# HIP4082.net
KiCad netlist of a schematic drawn in EasyEDA Pro
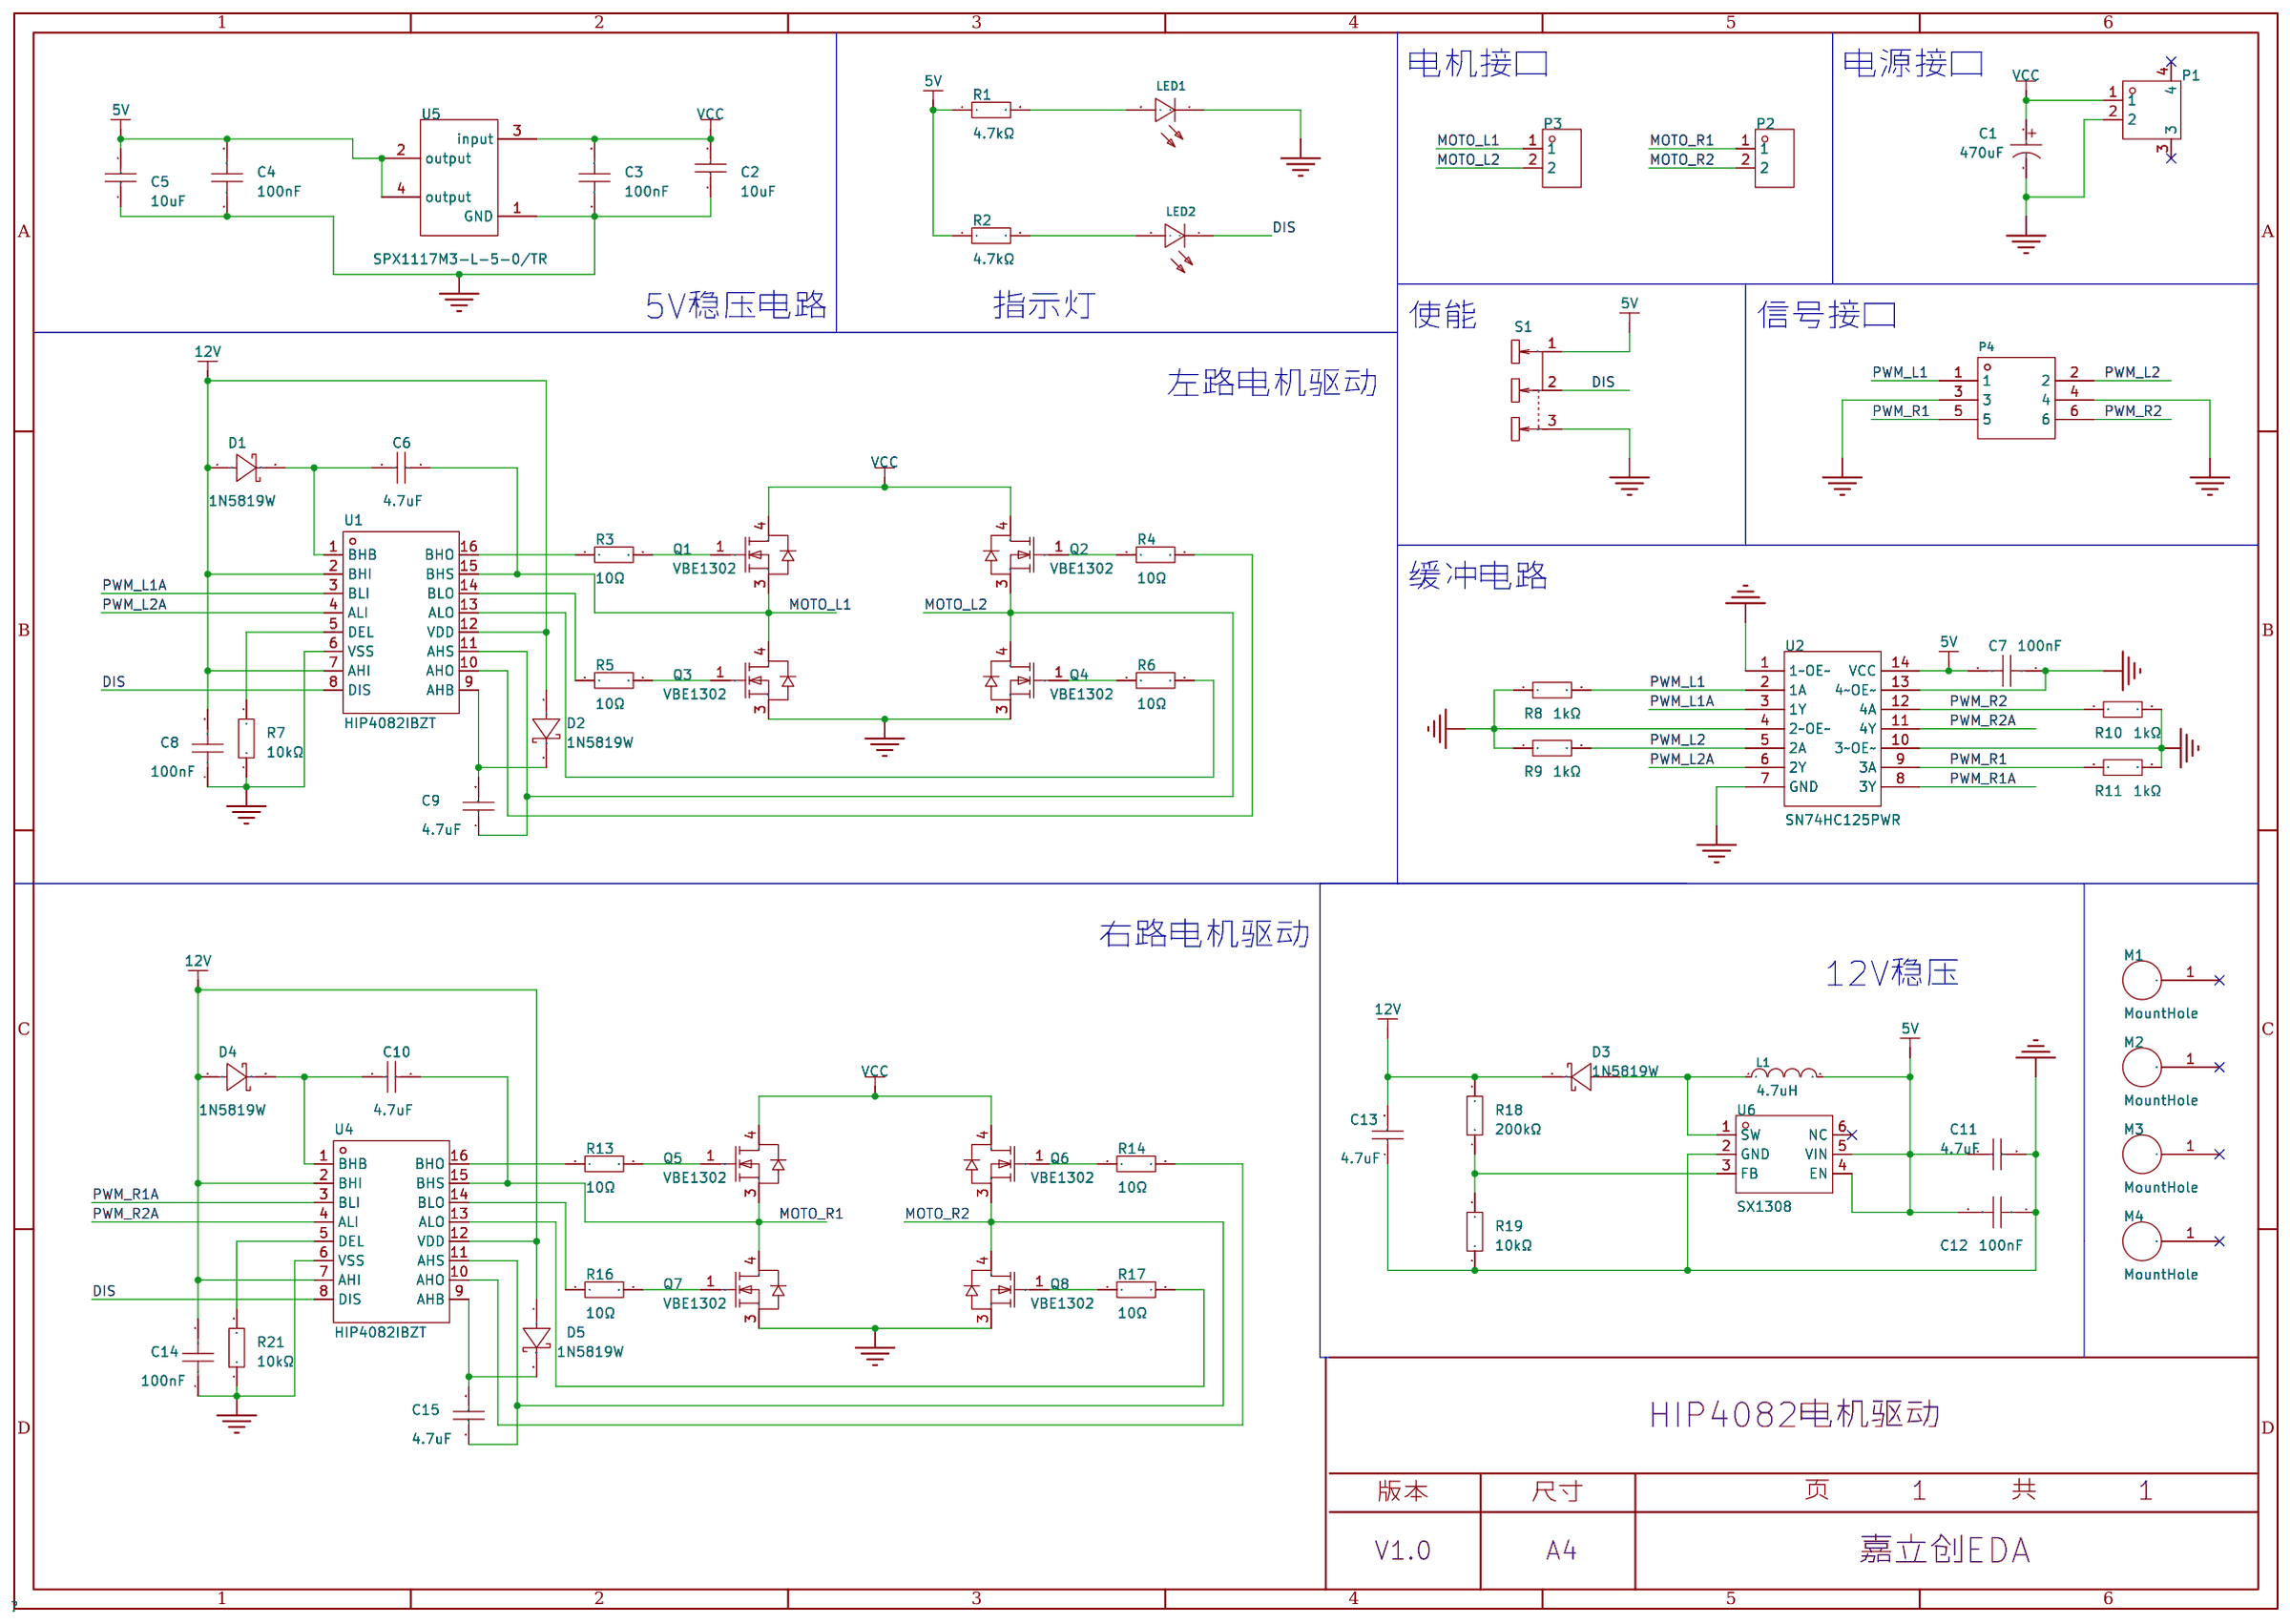
[diagram p0: schematic sheet]

(export (version "E")
  (design (tool "Eeschema 10.0.6"))
  (components
    (comp (ref "C1")
      (value "470uF")
      (footprint "easyedapro:CAP-TH_BD8.0-P3.50-D0.6-FD")
      (description "容值:470uF;精度:±20%;额定电压:25V;")
      (fields
        (field (name "Manufacturer Part") "KM477M025F12RR0VH2FP0")
        (field (name "Manufacturer") "CX(承兴)")
      )
      (libsource (lib "easyedapro") (part "470uF 25V 8*12"))
    )
    (comp (ref "C2")
      (value "10uF")
      (footprint "easyedapro:C0805")
      (description "容值:10uF;精度:±10%;额定电压:25V;材质(温度系数):X5R;")
      (fields
        (field (name "Manufacturer Part") "CL21A106KAYNNNE")
        (field (name "Manufacturer") "SAMSUNG(三星)")
      )
      (libsource (lib "easyedapro") (part "CL21A106KAYNNNE"))
    )
    (comp (ref "C3")
      (value "100nF")
      (footprint "easyedapro:C0603")
      (libsource (lib "easyedapro") (part "CapAcitance"))
    )
    (comp (ref "C4")
      (value "100nF")
      (footprint "easyedapro:C0603")
      (libsource (lib "easyedapro") (part "CapAcitance"))
    )
    (comp (ref "C5")
      (value "10uF")
      (footprint "easyedapro:C0805")
      (description "容值:10uF;精度:±10%;额定电压:25V;材质(温度系数):X5R;")
      (fields
        (field (name "Manufacturer Part") "CL21A106KAYNNNE")
        (field (name "Manufacturer") "SAMSUNG(三星)")
      )
      (libsource (lib "easyedapro") (part "CL21A106KAYNNNE"))
    )
    (comp (ref "C6")
      (value "4.7uF")
      (footprint "easyedapro:C0603")
      (description "容值:4.7uF;精度:±10%;额定电压:16V;材质(温度系数):X5R;")
      (fields
        (field (name "Manufacturer Part") "CL10A475KO8NNNC")
        (field (name "Manufacturer") "SAMSUNG(三星)")
      )
      (libsource (lib "easyedapro") (part "CL10A475KO8NNNC"))
    )
    (comp (ref "C7")
      (value "100nF")
      (footprint "easyedapro:C0603")
      (libsource (lib "easyedapro") (part "CapAcitance"))
    )
    (comp (ref "C8")
      (value "100nF")
      (footprint "easyedapro:C0603")
      (libsource (lib "easyedapro") (part "CapAcitance"))
    )
    (comp (ref "C9")
      (value "4.7uF")
      (footprint "easyedapro:C0603")
      (description "容值:4.7uF;精度:±10%;额定电压:16V;材质(温度系数):X5R;")
      (fields
        (field (name "Manufacturer Part") "CL10A475KO8NNNC")
        (field (name "Manufacturer") "SAMSUNG(三星)")
      )
      (libsource (lib "easyedapro") (part "CL10A475KO8NNNC"))
    )
    (comp (ref "C10")
      (value "4.7uF")
      (footprint "easyedapro:C0603")
      (description "容值:4.7uF;精度:±10%;额定电压:16V;材质(温度系数):X5R;")
      (fields
        (field (name "Manufacturer Part") "CL10A475KO8NNNC")
        (field (name "Manufacturer") "SAMSUNG(三星)")
      )
      (libsource (lib "easyedapro") (part "CL10A475KO8NNNC"))
    )
    (comp (ref "C11")
      (value "4.7uF")
      (footprint "easyedapro:C0603")
      (description "容值:4.7uF;精度:±10%;额定电压:16V;材质(温度系数):X5R;")
      (fields
        (field (name "Manufacturer Part") "CL10A475KO8NNNC")
        (field (name "Manufacturer") "SAMSUNG(三星)")
      )
      (libsource (lib "easyedapro") (part "CL10A475KO8NNNC"))
    )
    (comp (ref "C12")
      (value "100nF")
      (footprint "easyedapro:C0603")
      (libsource (lib "easyedapro") (part "CapAcitance"))
    )
    (comp (ref "C13")
      (value "4.7uF")
      (footprint "easyedapro:C0603")
      (description "容值:4.7uF;精度:±10%;额定电压:16V;材质(温度系数):X5R;")
      (fields
        (field (name "Manufacturer Part") "CL10A475KO8NNNC")
        (field (name "Manufacturer") "SAMSUNG(三星)")
      )
      (libsource (lib "easyedapro") (part "CL10A475KO8NNNC"))
    )
    (comp (ref "C14")
      (value "100nF")
      (footprint "easyedapro:C0603")
      (libsource (lib "easyedapro") (part "CapAcitance"))
    )
    (comp (ref "C15")
      (value "4.7uF")
      (footprint "easyedapro:C0603")
      (description "容值:4.7uF;精度:±10%;额定电压:16V;材质(温度系数):X5R;")
      (fields
        (field (name "Manufacturer Part") "CL10A475KO8NNNC")
        (field (name "Manufacturer") "SAMSUNG(三星)")
      )
      (libsource (lib "easyedapro") (part "CL10A475KO8NNNC"))
    )
    (comp (ref "D1")
      (value "1N5819W")
      (footprint "easyedapro:SOD-123_L2.7-W1.6-LS3.7-R-RD")
      (description "二极管配置:独立式;直流反向耐压(Vr):40V;平均整流电流(Io):350mA;正向压降(Vf):600mV@200mA;反向电流(Ir):5uA@30V;")
      (fields (field (name "Manufacturer") "JSMSEMI(杰盛微)"))
      (libsource (lib "easyedapro") (part "1N5819W_C963381"))
    )
    (comp (ref "D2")
      (value "1N5819W")
      (footprint "easyedapro:SOD-123_L2.7-W1.6-LS3.7-R-RD")
      (description "二极管配置:独立式;直流反向耐压(Vr):40V;平均整流电流(Io):350mA;正向压降(Vf):600mV@200mA;反向电流(Ir):5uA@30V;")
      (fields (field (name "Manufacturer") "JSMSEMI(杰盛微)"))
      (libsource (lib "easyedapro") (part "1N5819W_C963381"))
    )
    (comp (ref "D3")
      (value "1N5819W")
      (footprint "easyedapro:SOD-123_L2.7-W1.6-LS3.7-R-RD")
      (description "二极管配置:独立式;直流反向耐压(Vr):40V;平均整流电流(Io):350mA;正向压降(Vf):600mV@200mA;反向电流(Ir):5uA@30V;")
      (fields (field (name "Manufacturer") "JSMSEMI(杰盛微)"))
      (libsource (lib "easyedapro") (part "1N5819W_C963381"))
    )
    (comp (ref "D4")
      (value "1N5819W")
      (footprint "easyedapro:SOD-123_L2.7-W1.6-LS3.7-R-RD")
      (description "二极管配置:独立式;直流反向耐压(Vr):40V;平均整流电流(Io):350mA;正向压降(Vf):600mV@200mA;反向电流(Ir):5uA@30V;")
      (fields (field (name "Manufacturer") "JSMSEMI(杰盛微)"))
      (libsource (lib "easyedapro") (part "1N5819W_C963381"))
    )
    (comp (ref "D5")
      (value "1N5819W")
      (footprint "easyedapro:SOD-123_L2.7-W1.6-LS3.7-R-RD")
      (description "二极管配置:独立式;直流反向耐压(Vr):40V;平均整流电流(Io):350mA;正向压降(Vf):600mV@200mA;反向电流(Ir):5uA@30V;")
      (fields (field (name "Manufacturer") "JSMSEMI(杰盛微)"))
      (libsource (lib "easyedapro") (part "1N5819W_C963381"))
    )
    (comp (ref "L1")
      (value "4.7uH")
      (footprint "easyedapro:IND-SMD_L5.4-W5.2_FXL0530")
      (description "电感值:4.7uH;精度:±20%;额定电流:4.5A;饱和电流(Isat):5A;")
      (fields (field (name "Manufacturer Part") "FXL0530-4R7-M") (field (name "Manufacturer") "cjiang(长江微电)"))
      (libsource (lib "easyedapro") (part "FXL0530-4R7-M"))
    )
    (comp (ref "LED1")
      (value "NCD0603R1")
      (footprint "easyedapro:LED0603-RD_RED")
      (description "发光颜色:红灯;")
      (fields (field (name "Manufacturer") "国星光电"))
      (libsource (lib "easyedapro") (part "FC-DA1608HRK-620D"))
    )
    (comp (ref "LED2")
      (value "NCD0603B1")
      (footprint "easyedapro:LED0603-RD")
      (description "发光颜色:蓝灯;")
      (fields (field (name "Manufacturer") "国星光电"))
      (libsource (lib "easyedapro") (part "FC-DA1608BK-470H10"))
    )
    (comp (ref "M1")
      (value "MountHole")
      (footprint "easyedapro:M3-MountSlot")
      (libsource (lib "easyedapro") (part "MountHole"))
    )
    (comp (ref "M2")
      (value "MountHole")
      (footprint "easyedapro:M3-MountSlot")
      (libsource (lib "easyedapro") (part "MountHole"))
    )
    (comp (ref "M3")
      (value "MountHole")
      (footprint "easyedapro:M3-MountSlot")
      (libsource (lib "easyedapro") (part "MountHole"))
    )
    (comp (ref "M4")
      (value "MountHole")
      (footprint "easyedapro:M3-MountSlot")
      (libsource (lib "easyedapro") (part "MountHole"))
    )
    (comp (ref "P1")
      (value "XT30PW-M")
      (footprint "easyedapro:CONN-TH_XT30PW-M")
      (description "Socket,DCsupply,XT30,male,PIN:2")
      (fields (field (name "Manufacturer") "AMASS(艾迈斯)"))
      (libsource (lib "easyedapro") (part "XT30PW-M"))
    )
    (comp (ref "P2")
      (value "XT30U-M")
      (footprint "easyedapro:CONN-TH_XT30U-M")
      (description "模型插头轻量版锂电池插头")
      (fields (field (name "Manufacturer") "AMASS(艾迈斯)"))
      (libsource (lib "easyedapro") (part "XT30U-M"))
    )
    (comp (ref "P3")
      (value "XT30U-M")
      (footprint "easyedapro:CONN-TH_XT30U-M")
      (description "模型插头轻量版锂电池插头")
      (fields (field (name "Manufacturer") "AMASS(艾迈斯)"))
      (libsource (lib "easyedapro") (part "XT30U-M"))
    )
    (comp (ref "P4")
      (value "75869-131LF")
      (footprint "easyedapro:CONN-TH_6P-P2.54_75869-131LF")
      (description "参考系列:-;间距:2.54mm;插针结构:2x3P;排数:2;每排PIN数:3;行距:2.54mm;安装方式:-;触头材质:磷青铜;")
      (fields (field (name "Manufacturer") "Amphenol"))
      (libsource (lib "easyedapro") (part "75869-131LF"))
    )
    (comp (ref "Q1")
      (value "VBE1302")
      (footprint "easyedapro:TO-252-2_L6.6-W6.1-P4.58-LS9.9-TL-1")
      (fields (field (name "Manufacturer") "VBsemi(微碧)"))
      (libsource (lib "easyedapro") (part "VBE1302"))
    )
    (comp (ref "Q2")
      (value "VBE1302")
      (footprint "easyedapro:TO-252-2_L6.6-W6.1-P4.58-LS9.9-TL-1")
      (fields (field (name "Manufacturer") "VBsemi(微碧)"))
      (libsource (lib "easyedapro") (part "VBE1302"))
    )
    (comp (ref "Q3")
      (value "VBE1302")
      (footprint "easyedapro:TO-252-2_L6.6-W6.1-P4.58-LS9.9-TL-1")
      (fields (field (name "Manufacturer") "VBsemi(微碧)"))
      (libsource (lib "easyedapro") (part "VBE1302"))
    )
    (comp (ref "Q4")
      (value "VBE1302")
      (footprint "easyedapro:TO-252-2_L6.6-W6.1-P4.58-LS9.9-TL-1")
      (fields (field (name "Manufacturer") "VBsemi(微碧)"))
      (libsource (lib "easyedapro") (part "VBE1302"))
    )
    (comp (ref "Q5")
      (value "VBE1302")
      (footprint "easyedapro:TO-252-2_L6.6-W6.1-P4.58-LS9.9-TL-1")
      (fields (field (name "Manufacturer") "VBsemi(微碧)"))
      (libsource (lib "easyedapro") (part "VBE1302"))
    )
    (comp (ref "Q6")
      (value "VBE1302")
      (footprint "easyedapro:TO-252-2_L6.6-W6.1-P4.58-LS9.9-TL-1")
      (fields (field (name "Manufacturer") "VBsemi(微碧)"))
      (libsource (lib "easyedapro") (part "VBE1302"))
    )
    (comp (ref "Q7")
      (value "VBE1302")
      (footprint "easyedapro:TO-252-2_L6.6-W6.1-P4.58-LS9.9-TL-1")
      (fields (field (name "Manufacturer") "VBsemi(微碧)"))
      (libsource (lib "easyedapro") (part "VBE1302"))
    )
    (comp (ref "Q8")
      (value "VBE1302")
      (footprint "easyedapro:TO-252-2_L6.6-W6.1-P4.58-LS9.9-TL-1")
      (fields (field (name "Manufacturer") "VBsemi(微碧)"))
      (libsource (lib "easyedapro") (part "VBE1302"))
    )
    (comp (ref "R1")
      (value "4.7kΩ")
      (footprint "easyedapro:R0603")
      (description "电阻类型:厚膜电阻;阻值:4.7kΩ;精度:±1%;功率:100mW;")
      (fields
        (field (name "Manufacturer Part") "0603WAF4701T5E")
        (field (name "Manufacturer") "UNI-ROYAL(厚声)")
      )
      (libsource (lib "easyedapro") (part "0603WAF4701T5E"))
    )
    (comp (ref "R2")
      (value "4.7kΩ")
      (footprint "easyedapro:R0603")
      (description "电阻类型:厚膜电阻;阻值:4.7kΩ;精度:±1%;功率:100mW;")
      (fields
        (field (name "Manufacturer Part") "0603WAF4701T5E")
        (field (name "Manufacturer") "UNI-ROYAL(厚声)")
      )
      (libsource (lib "easyedapro") (part "0603WAF4701T5E"))
    )
    (comp (ref "R3")
      (value "10Ω")
      (footprint "easyedapro:R0603")
      (description "电阻类型:厚膜电阻;阻值:10Ω;精度:±1%;功率:100mW;")
      (fields
        (field (name "Manufacturer Part") "0603WAF100JT5E")
        (field (name "Manufacturer") "UNI-ROYAL(厚声)")
      )
      (libsource (lib "easyedapro") (part "0603WAF100JT5E"))
    )
    (comp (ref "R4")
      (value "10Ω")
      (footprint "easyedapro:R0603")
      (description "电阻类型:厚膜电阻;阻值:10Ω;精度:±1%;功率:100mW;")
      (fields
        (field (name "Manufacturer Part") "0603WAF100JT5E")
        (field (name "Manufacturer") "UNI-ROYAL(厚声)")
      )
      (libsource (lib "easyedapro") (part "0603WAF100JT5E"))
    )
    (comp (ref "R5")
      (value "10Ω")
      (footprint "easyedapro:R0603")
      (description "电阻类型:厚膜电阻;阻值:10Ω;精度:±1%;功率:100mW;")
      (fields
        (field (name "Manufacturer Part") "0603WAF100JT5E")
        (field (name "Manufacturer") "UNI-ROYAL(厚声)")
      )
      (libsource (lib "easyedapro") (part "0603WAF100JT5E"))
    )
    (comp (ref "R6")
      (value "10Ω")
      (footprint "easyedapro:R0603")
      (description "电阻类型:厚膜电阻;阻值:10Ω;精度:±1%;功率:100mW;")
      (fields
        (field (name "Manufacturer Part") "0603WAF100JT5E")
        (field (name "Manufacturer") "UNI-ROYAL(厚声)")
      )
      (libsource (lib "easyedapro") (part "0603WAF100JT5E"))
    )
    (comp (ref "R7")
      (value "10kΩ")
      (footprint "easyedapro:R0603")
      (description "电阻类型:厚膜电阻;阻值:10kΩ;精度:±1%;功率:100mW;")
      (fields
        (field (name "Manufacturer Part") "0603WAF1002T5E")
        (field (name "Manufacturer") "UNI-ROYAL(厚声)")
      )
      (libsource (lib "easyedapro") (part "0603WAF1002T5E"))
    )
    (comp (ref "R8")
      (value "1kΩ")
      (footprint "easyedapro:R0603")
      (description "电阻类型:厚膜电阻;阻值:1kΩ;精度:±1%;功率:100mW;")
      (fields
        (field (name "Manufacturer Part") "0603WAF1001T5E")
        (field (name "Manufacturer") "UNI-ROYAL(厚声)")
      )
      (libsource (lib "easyedapro") (part "0603WAF1001T5E"))
    )
    (comp (ref "R9")
      (value "1kΩ")
      (footprint "easyedapro:R0603")
      (description "电阻类型:厚膜电阻;阻值:1kΩ;精度:±1%;功率:100mW;")
      (fields
        (field (name "Manufacturer Part") "0603WAF1001T5E")
        (field (name "Manufacturer") "UNI-ROYAL(厚声)")
      )
      (libsource (lib "easyedapro") (part "0603WAF1001T5E"))
    )
    (comp (ref "R10")
      (value "1kΩ")
      (footprint "easyedapro:R0603")
      (description "电阻类型:厚膜电阻;阻值:1kΩ;精度:±1%;功率:100mW;")
      (fields
        (field (name "Manufacturer Part") "0603WAF1001T5E")
        (field (name "Manufacturer") "UNI-ROYAL(厚声)")
      )
      (libsource (lib "easyedapro") (part "0603WAF1001T5E"))
    )
    (comp (ref "R11")
      (value "1kΩ")
      (footprint "easyedapro:R0603")
      (description "电阻类型:厚膜电阻;阻值:1kΩ;精度:±1%;功率:100mW;")
      (fields
        (field (name "Manufacturer Part") "0603WAF1001T5E")
        (field (name "Manufacturer") "UNI-ROYAL(厚声)")
      )
      (libsource (lib "easyedapro") (part "0603WAF1001T5E"))
    )
    (comp (ref "R13")
      (value "10Ω")
      (footprint "easyedapro:R0603")
      (description "电阻类型:厚膜电阻;阻值:10Ω;精度:±1%;功率:100mW;")
      (fields
        (field (name "Manufacturer Part") "0603WAF100JT5E")
        (field (name "Manufacturer") "UNI-ROYAL(厚声)")
      )
      (libsource (lib "easyedapro") (part "0603WAF100JT5E"))
    )
    (comp (ref "R14")
      (value "10Ω")
      (footprint "easyedapro:R0603")
      (description "电阻类型:厚膜电阻;阻值:10Ω;精度:±1%;功率:100mW;")
      (fields
        (field (name "Manufacturer Part") "0603WAF100JT5E")
        (field (name "Manufacturer") "UNI-ROYAL(厚声)")
      )
      (libsource (lib "easyedapro") (part "0603WAF100JT5E"))
    )
    (comp (ref "R16")
      (value "10Ω")
      (footprint "easyedapro:R0603")
      (description "电阻类型:厚膜电阻;阻值:10Ω;精度:±1%;功率:100mW;")
      (fields
        (field (name "Manufacturer Part") "0603WAF100JT5E")
        (field (name "Manufacturer") "UNI-ROYAL(厚声)")
      )
      (libsource (lib "easyedapro") (part "0603WAF100JT5E"))
    )
    (comp (ref "R17")
      (value "10Ω")
      (footprint "easyedapro:R0603")
      (description "电阻类型:厚膜电阻;阻值:10Ω;精度:±1%;功率:100mW;")
      (fields
        (field (name "Manufacturer Part") "0603WAF100JT5E")
        (field (name "Manufacturer") "UNI-ROYAL(厚声)")
      )
      (libsource (lib "easyedapro") (part "0603WAF100JT5E"))
    )
    (comp (ref "R18")
      (value "200kΩ")
      (footprint "easyedapro:R0603")
      (description "电阻类型:厚膜电阻;阻值:200kΩ;精度:±1%;功率:100mW;")
      (fields
        (field (name "Manufacturer Part") "0603WAF2003T5E")
        (field (name "Manufacturer") "UNI-ROYAL(厚声)")
      )
      (libsource (lib "easyedapro") (part "0603WAF2003T5E"))
    )
    (comp (ref "R19")
      (value "10kΩ")
      (footprint "easyedapro:R0603")
      (description "电阻类型:厚膜电阻;阻值:10kΩ;精度:±1%;功率:100mW;")
      (fields
        (field (name "Manufacturer Part") "0603WAF1002T5E")
        (field (name "Manufacturer") "UNI-ROYAL(厚声)")
      )
      (libsource (lib "easyedapro") (part "0603WAF1002T5E"))
    )
    (comp (ref "R21")
      (value "10kΩ")
      (footprint "easyedapro:R0603")
      (description "电阻类型:厚膜电阻;阻值:10kΩ;精度:±1%;功率:100mW;")
      (fields
        (field (name "Manufacturer Part") "0603WAF1002T5E")
        (field (name "Manufacturer") "UNI-ROYAL(厚声)")
      )
      (libsource (lib "easyedapro") (part "0603WAF1002T5E"))
    )
    (comp (ref "S1")
      (value "SS-12D10L3")
      (footprint "easyedapro:SW-TH_SS-12D10L3")
      (description "额定电流(DC):3A;额定电压(DC):125V;额定电流(AC):3A;额定电压(AC):125V;电路结构:单刀双掷;安装方式:直插;机械寿命:1万次;开关颜色:黑色;")
      (fields (field (name "Manufacturer") "XKB Connectivity(中国星坤)"))
      (libsource (lib "easyedapro") (part "SS-12D10L3"))
    )
    (comp (ref "U1")
      (value "HIP4082IBZT")
      (footprint "easyedapro:SOIC-16_L9.9-W3.9-P1.27-LS6.0-BL")
      (description "驱动配置:半桥；全桥;负载类型:MOSFET;电源电压:8.5V~15V;")
      (fields (field (name "Manufacturer") "RENESAS(瑞萨)/IDT"))
      (libsource (lib "easyedapro") (part "HIP4082IBZT"))
    )
    (comp (ref "U2")
      (value "SN74HC125PWR")
      (footprint "easyedapro:TSSOP-14")
      (libsource (lib "easyedapro") (part "SN74HC125PWR"))
    )
    (comp (ref "U4")
      (value "HIP4082IBZT")
      (footprint "easyedapro:SOIC-16_L9.9-W3.9-P1.27-LS6.0-BL")
      (description "驱动配置:半桥；全桥;负载类型:MOSFET;电源电压:8.5V~15V;")
      (fields (field (name "Manufacturer") "RENESAS(瑞萨)/IDT"))
      (libsource (lib "easyedapro") (part "HIP4082IBZT"))
    )
    (comp (ref "U5")
      (value "SPX1117M3-L-5-0/TR")
      (footprint "easyedapro:SOT-223-4_L6.5-W3.5-P2.30-LS7.0-BR")
      (description "输出类型:固定;输出极性:正;最大输入电压:20V;输出电压:5V;输出电流:800mA;电源纹波抑制比(PSRR):75dB@(120Hz);")
      (fields (field (name "Manufacturer") "MaxLinear"))
      (libsource (lib "easyedapro") (part "SPX1117M3-L-5-0/TR"))
    )
    (comp (ref "U6")
      (value "SX1308")
      (footprint "easyedapro:SOT-23-6_L2.9-W1.6-P0.95-LS2.8-BL")
      (description "功能类型:升压型;同步整流:否;输出通道数:1;拓扑结构:升压式;输入电压:2V~24V;输出电压:28V;输出电流(最大值):-;开关频率:1.2MHz;")
      (fields (field (name "Manufacturer") "SX(硕芯科技)"))
      (libsource (lib "easyedapro") (part "SX1308"))
    )
  )
  (nets
    (net (code "1") (name "/DIS") (class "Default")
      (node (ref "LED2") (pin "1") (pinfunction "-_1") (pintype "input"))
      (node (ref "S1") (pin "2") (pinfunction "2_2") (pintype "input"))
      (node (ref "U1") (pin "8") (pinfunction "DIS_8") (pintype "input"))
      (node (ref "U4") (pin "8") (pinfunction "DIS_8") (pintype "input"))
    )
    (net (code "2") (name "/MOTO_L1") (class "Default")
      (node (ref "C6") (pin "2") (pinfunction "2_2") (pintype "input"))
      (node (ref "P3") (pin "1") (pinfunction "1_1") (pintype "input"))
      (node (ref "Q1") (pin "3") (pinfunction "S_3") (pintype "input"))
      (node (ref "Q3") (pin "4") (pinfunction "D_4") (pintype "input"))
      (node (ref "U1") (pin "15") (pinfunction "BHS_15") (pintype "input"))
    )
    (net (code "3") (name "/MOTO_L2") (class "Default")
      (node (ref "C9") (pin "1") (pinfunction "1_1") (pintype "input"))
      (node (ref "P3") (pin "2") (pinfunction "2_2") (pintype "input"))
      (node (ref "Q2") (pin "3") (pinfunction "S_3") (pintype "input"))
      (node (ref "Q4") (pin "4") (pinfunction "D_4") (pintype "input"))
      (node (ref "U1") (pin "11") (pinfunction "AHS_11") (pintype "input"))
    )
    (net (code "4") (name "/MOTO_R1") (class "Default")
      (node (ref "C10") (pin "2") (pinfunction "2_2") (pintype "input"))
      (node (ref "P2") (pin "1") (pinfunction "1_1") (pintype "input"))
      (node (ref "Q5") (pin "3") (pinfunction "S_3") (pintype "input"))
      (node (ref "Q7") (pin "4") (pinfunction "D_4") (pintype "input"))
      (node (ref "U4") (pin "15") (pinfunction "BHS_15") (pintype "input"))
    )
    (net (code "5") (name "/MOTO_R2") (class "Default")
      (node (ref "C15") (pin "1") (pinfunction "1_1") (pintype "input"))
      (node (ref "P2") (pin "2") (pinfunction "2_2") (pintype "input"))
      (node (ref "Q6") (pin "3") (pinfunction "S_3") (pintype "input"))
      (node (ref "Q8") (pin "4") (pinfunction "D_4") (pintype "input"))
      (node (ref "U4") (pin "11") (pinfunction "AHS_11") (pintype "input"))
    )
    (net (code "6") (name "/PWM_L1") (class "Default")
      (node (ref "P4") (pin "1") (pinfunction "1_1") (pintype "input"))
      (node (ref "R8") (pin "2") (pinfunction "2_2") (pintype "input"))
      (node (ref "U2") (pin "2") (pinfunction "1A_2") (pintype "input"))
    )
    (net (code "7") (name "/PWM_L1A") (class "Default")
      (node (ref "U1") (pin "3") (pinfunction "BLI_3") (pintype "input"))
      (node (ref "U2") (pin "3") (pinfunction "1Y_3") (pintype "input"))
    )
    (net (code "8") (name "/PWM_L2") (class "Default")
      (node (ref "P4") (pin "2") (pinfunction "2_2") (pintype "input"))
      (node (ref "R9") (pin "2") (pinfunction "2_2") (pintype "input"))
      (node (ref "U2") (pin "5") (pinfunction "2A_5") (pintype "input"))
    )
    (net (code "9") (name "/PWM_L2A") (class "Default")
      (node (ref "U1") (pin "4") (pinfunction "ALI_4") (pintype "input"))
      (node (ref "U2") (pin "6") (pinfunction "2Y_6") (pintype "input"))
    )
    (net (code "10") (name "/PWM_R1") (class "Default")
      (node (ref "P4") (pin "5") (pinfunction "5_5") (pintype "input"))
      (node (ref "R11") (pin "1") (pinfunction "1_1") (pintype "input"))
      (node (ref "U2") (pin "9") (pinfunction "3A_9") (pintype "input"))
    )
    (net (code "11") (name "/PWM_R1A") (class "Default")
      (node (ref "U2") (pin "8") (pinfunction "3Y_8") (pintype "input"))
      (node (ref "U4") (pin "3") (pinfunction "BLI_3") (pintype "input"))
    )
    (net (code "12") (name "/PWM_R2") (class "Default")
      (node (ref "P4") (pin "6") (pinfunction "6_6") (pintype "input"))
      (node (ref "R10") (pin "1") (pinfunction "1_1") (pintype "input"))
      (node (ref "U2") (pin "12") (pinfunction "4A_12") (pintype "input"))
    )
    (net (code "13") (name "/PWM_R2A") (class "Default")
      (node (ref "U2") (pin "11") (pinfunction "4Y_11") (pintype "input"))
      (node (ref "U4") (pin "4") (pinfunction "ALI_4") (pintype "input"))
    )
    (net (code "14") (name "5V") (class "Default")
      (node (ref "C11") (pin "1") (pinfunction "1_1") (pintype "input"))
      (node (ref "C12") (pin "2") (pinfunction "2_2") (pintype "input"))
      (node (ref "C4") (pin "2") (pinfunction "2_2") (pintype "input"))
      (node (ref "C5") (pin "2") (pinfunction "2_2") (pintype "input"))
      (node (ref "C7") (pin "2") (pinfunction "2_2") (pintype "input"))
      (node (ref "L1") (pin "2") (pinfunction "2_2") (pintype "input"))
      (node (ref "R1") (pin "1") (pinfunction "1_1") (pintype "input"))
      (node (ref "R2") (pin "1") (pinfunction "1_1") (pintype "input"))
      (node (ref "S1") (pin "1") (pinfunction "1_1") (pintype "input"))
      (node (ref "U2") (pin "14") (pinfunction "VCC_14") (pintype "input"))
      (node (ref "U5") (pin "2") (pinfunction "output_2") (pintype "input"))
      (node (ref "U5") (pin "4") (pinfunction "output_4") (pintype "input"))
      (node (ref "U6") (pin "4") (pinfunction "EN_4") (pintype "input"))
      (node (ref "U6") (pin "5") (pinfunction "VIN_5") (pintype "input"))
    )
    (net (code "15") (name "12V") (class "Default")
      (node (ref "C13") (pin "2") (pinfunction "2_2") (pintype "input"))
      (node (ref "C14") (pin "2") (pinfunction "2_2") (pintype "input"))
      (node (ref "C8") (pin "2") (pinfunction "2_2") (pintype "input"))
      (node (ref "D1") (pin "1") (pinfunction "A_1") (pintype "input"))
      (node (ref "D2") (pin "1") (pinfunction "A_1") (pintype "input"))
      (node (ref "D3") (pin "2") (pinfunction "C_2") (pintype "input"))
      (node (ref "D4") (pin "1") (pinfunction "A_1") (pintype "input"))
      (node (ref "D5") (pin "1") (pinfunction "A_1") (pintype "input"))
      (node (ref "R18") (pin "2") (pinfunction "2_2") (pintype "input"))
      (node (ref "U1") (pin "12") (pinfunction "VDD_12") (pintype "input"))
      (node (ref "U1") (pin "2") (pinfunction "BHI_2") (pintype "input"))
      (node (ref "U1") (pin "7") (pinfunction "AHI_7") (pintype "input"))
      (node (ref "U4") (pin "12") (pinfunction "VDD_12") (pintype "input"))
      (node (ref "U4") (pin "2") (pinfunction "BHI_2") (pintype "input"))
      (node (ref "U4") (pin "7") (pinfunction "AHI_7") (pintype "input"))
    )
    (net (code "16") (name "GND") (class "Default")
      (node (ref "C1") (pin "2") (pinfunction "2_2") (pintype "input"))
      (node (ref "C11") (pin "2") (pinfunction "2_2") (pintype "input"))
      (node (ref "C12") (pin "1") (pinfunction "1_1") (pintype "input"))
      (node (ref "C13") (pin "1") (pinfunction "1_1") (pintype "input"))
      (node (ref "C14") (pin "1") (pinfunction "1_1") (pintype "input"))
      (node (ref "C2") (pin "1") (pinfunction "1_1") (pintype "input"))
      (node (ref "C3") (pin "1") (pinfunction "1_1") (pintype "input"))
      (node (ref "C4") (pin "1") (pinfunction "1_1") (pintype "input"))
      (node (ref "C5") (pin "1") (pinfunction "1_1") (pintype "input"))
      (node (ref "C7") (pin "1") (pinfunction "1_1") (pintype "input"))
      (node (ref "C8") (pin "1") (pinfunction "1_1") (pintype "input"))
      (node (ref "LED1") (pin "1") (pinfunction "K_1") (pintype "input"))
      (node (ref "P1") (pin "2") (pinfunction "2_2") (pintype "input"))
      (node (ref "P4") (pin "3") (pinfunction "3_3") (pintype "input"))
      (node (ref "P4") (pin "4") (pinfunction "4_4") (pintype "input"))
      (node (ref "Q3") (pin "3") (pinfunction "S_3") (pintype "input"))
      (node (ref "Q4") (pin "3") (pinfunction "S_3") (pintype "input"))
      (node (ref "Q7") (pin "3") (pinfunction "S_3") (pintype "input"))
      (node (ref "Q8") (pin "3") (pinfunction "S_3") (pintype "input"))
      (node (ref "R10") (pin "2") (pinfunction "2_2") (pintype "input"))
      (node (ref "R11") (pin "2") (pinfunction "2_2") (pintype "input"))
      (node (ref "R19") (pin "1") (pinfunction "1_1") (pintype "input"))
      (node (ref "R21") (pin "1") (pinfunction "1_1") (pintype "input"))
      (node (ref "R7") (pin "1") (pinfunction "1_1") (pintype "input"))
      (node (ref "R8") (pin "1") (pinfunction "1_1") (pintype "input"))
      (node (ref "R9") (pin "1") (pinfunction "1_1") (pintype "input"))
      (node (ref "S1") (pin "3") (pinfunction "3_3") (pintype "input"))
      (node (ref "U1") (pin "6") (pinfunction "VSS_6") (pintype "input"))
      (node (ref "U2") (pin "1") (pinfunction "1~OE~_1") (pintype "input"))
      (node (ref "U2") (pin "10") (pinfunction "3~OE~_10") (pintype "input"))
      (node (ref "U2") (pin "13") (pinfunction "4~OE~_13") (pintype "input"))
      (node (ref "U2") (pin "4") (pinfunction "2~OE~_4") (pintype "input"))
      (node (ref "U2") (pin "7") (pinfunction "GND_7") (pintype "input"))
      (node (ref "U4") (pin "6") (pinfunction "VSS_6") (pintype "input"))
      (node (ref "U5") (pin "1") (pinfunction "GND_1") (pintype "input"))
      (node (ref "U6") (pin "2") (pinfunction "GND_2") (pintype "input"))
    )
    (net (code "17") (name "Net-(D1-C)") (class "Default")
      (node (ref "C6") (pin "1") (pinfunction "1_1") (pintype "input"))
      (node (ref "D1") (pin "2") (pinfunction "C_2") (pintype "input"))
      (node (ref "U1") (pin "1") (pinfunction "BHB_1") (pintype "input"))
    )
    (net (code "18") (name "Net-(D2-C)") (class "Default")
      (node (ref "C9") (pin "2") (pinfunction "2_2") (pintype "input"))
      (node (ref "D2") (pin "2") (pinfunction "C_2") (pintype "input"))
      (node (ref "U1") (pin "9") (pinfunction "AHB_9") (pintype "input"))
    )
    (net (code "19") (name "Net-(D3-A)") (class "Default")
      (node (ref "D3") (pin "1") (pinfunction "A_1") (pintype "input"))
      (node (ref "L1") (pin "1") (pinfunction "1_1") (pintype "input"))
      (node (ref "U6") (pin "1") (pinfunction "SW_1") (pintype "input"))
    )
    (net (code "20") (name "Net-(D4-C)") (class "Default")
      (node (ref "C10") (pin "1") (pinfunction "1_1") (pintype "input"))
      (node (ref "D4") (pin "2") (pinfunction "C_2") (pintype "input"))
      (node (ref "U4") (pin "1") (pinfunction "BHB_1") (pintype "input"))
    )
    (net (code "21") (name "Net-(D5-C)") (class "Default")
      (node (ref "C15") (pin "2") (pinfunction "2_2") (pintype "input"))
      (node (ref "D5") (pin "2") (pinfunction "C_2") (pintype "input"))
      (node (ref "U4") (pin "9") (pinfunction "AHB_9") (pintype "input"))
    )
    (net (code "22") (name "Net-(LED1-A)") (class "Default")
      (node (ref "LED1") (pin "2") (pinfunction "A_2") (pintype "input"))
      (node (ref "R1") (pin "2") (pinfunction "2_2") (pintype "input"))
    )
    (net (code "23") (name "Net-(LED2-+)") (class "Default")
      (node (ref "LED2") (pin "2") (pinfunction "+_2") (pintype "input"))
      (node (ref "R2") (pin "2") (pinfunction "2_2") (pintype "input"))
    )
    (net (code "24") (name "Net-(Q1-G)") (class "Default")
      (node (ref "Q1") (pin "1") (pinfunction "G_1") (pintype "input"))
      (node (ref "R3") (pin "2") (pinfunction "2_2") (pintype "input"))
    )
    (net (code "25") (name "Net-(Q2-G)") (class "Default")
      (node (ref "Q2") (pin "1") (pinfunction "G_1") (pintype "input"))
      (node (ref "R4") (pin "1") (pinfunction "1_1") (pintype "input"))
    )
    (net (code "26") (name "Net-(Q3-G)") (class "Default")
      (node (ref "Q3") (pin "1") (pinfunction "G_1") (pintype "input"))
      (node (ref "R5") (pin "2") (pinfunction "2_2") (pintype "input"))
    )
    (net (code "27") (name "Net-(Q4-G)") (class "Default")
      (node (ref "Q4") (pin "1") (pinfunction "G_1") (pintype "input"))
      (node (ref "R6") (pin "1") (pinfunction "1_1") (pintype "input"))
    )
    (net (code "28") (name "Net-(Q5-G)") (class "Default")
      (node (ref "Q5") (pin "1") (pinfunction "G_1") (pintype "input"))
      (node (ref "R13") (pin "2") (pinfunction "2_2") (pintype "input"))
    )
    (net (code "29") (name "Net-(Q6-G)") (class "Default")
      (node (ref "Q6") (pin "1") (pinfunction "G_1") (pintype "input"))
      (node (ref "R14") (pin "1") (pinfunction "1_1") (pintype "input"))
    )
    (net (code "30") (name "Net-(Q7-G)") (class "Default")
      (node (ref "Q7") (pin "1") (pinfunction "G_1") (pintype "input"))
      (node (ref "R16") (pin "2") (pinfunction "2_2") (pintype "input"))
    )
    (net (code "31") (name "Net-(Q8-G)") (class "Default")
      (node (ref "Q8") (pin "1") (pinfunction "G_1") (pintype "input"))
      (node (ref "R17") (pin "1") (pinfunction "1_1") (pintype "input"))
    )
    (net (code "32") (name "Net-(U1-AHO)") (class "Default")
      (node (ref "R4") (pin "2") (pinfunction "2_2") (pintype "input"))
      (node (ref "U1") (pin "10") (pinfunction "AHO_10") (pintype "input"))
    )
    (net (code "33") (name "Net-(U1-ALO)") (class "Default")
      (node (ref "R6") (pin "2") (pinfunction "2_2") (pintype "input"))
      (node (ref "U1") (pin "13") (pinfunction "ALO_13") (pintype "input"))
    )
    (net (code "34") (name "Net-(U1-BHO)") (class "Default")
      (node (ref "R3") (pin "1") (pinfunction "1_1") (pintype "input"))
      (node (ref "U1") (pin "16") (pinfunction "BHO_16") (pintype "input"))
    )
    (net (code "35") (name "Net-(U1-BLO)") (class "Default")
      (node (ref "R5") (pin "1") (pinfunction "1_1") (pintype "input"))
      (node (ref "U1") (pin "14") (pinfunction "BLO_14") (pintype "input"))
    )
    (net (code "36") (name "Net-(U1-DEL)") (class "Default")
      (node (ref "R7") (pin "2") (pinfunction "2_2") (pintype "input"))
      (node (ref "U1") (pin "5") (pinfunction "DEL_5") (pintype "input"))
    )
    (net (code "37") (name "Net-(U4-AHO)") (class "Default")
      (node (ref "R14") (pin "2") (pinfunction "2_2") (pintype "input"))
      (node (ref "U4") (pin "10") (pinfunction "AHO_10") (pintype "input"))
    )
    (net (code "38") (name "Net-(U4-ALO)") (class "Default")
      (node (ref "R17") (pin "2") (pinfunction "2_2") (pintype "input"))
      (node (ref "U4") (pin "13") (pinfunction "ALO_13") (pintype "input"))
    )
    (net (code "39") (name "Net-(U4-BHO)") (class "Default")
      (node (ref "R13") (pin "1") (pinfunction "1_1") (pintype "input"))
      (node (ref "U4") (pin "16") (pinfunction "BHO_16") (pintype "input"))
    )
    (net (code "40") (name "Net-(U4-BLO)") (class "Default")
      (node (ref "R16") (pin "1") (pinfunction "1_1") (pintype "input"))
      (node (ref "U4") (pin "14") (pinfunction "BLO_14") (pintype "input"))
    )
    (net (code "41") (name "Net-(U4-DEL)") (class "Default")
      (node (ref "R21") (pin "2") (pinfunction "2_2") (pintype "input"))
      (node (ref "U4") (pin "5") (pinfunction "DEL_5") (pintype "input"))
    )
    (net (code "42") (name "Net-(U6-FB)") (class "Default")
      (node (ref "R18") (pin "1") (pinfunction "1_1") (pintype "input"))
      (node (ref "R19") (pin "2") (pinfunction "2_2") (pintype "input"))
      (node (ref "U6") (pin "3") (pinfunction "FB_3") (pintype "input"))
    )
    (net (code "43") (name "VCC") (class "Default")
      (node (ref "C1") (pin "1") (pinfunction "1_1") (pintype "input"))
      (node (ref "C2") (pin "2") (pinfunction "2_2") (pintype "input"))
      (node (ref "C3") (pin "2") (pinfunction "2_2") (pintype "input"))
      (node (ref "P1") (pin "1") (pinfunction "1_1") (pintype "input"))
      (node (ref "Q1") (pin "4") (pinfunction "D_4") (pintype "input"))
      (node (ref "Q2") (pin "4") (pinfunction "D_4") (pintype "input"))
      (node (ref "Q5") (pin "4") (pinfunction "D_4") (pintype "input"))
      (node (ref "Q6") (pin "4") (pinfunction "D_4") (pintype "input"))
      (node (ref "U5") (pin "3") (pinfunction "input_3") (pintype "input"))
    )
    (net (code "44") (name "unconnected-(M1-Pad1)") (class "Default")
      (node (ref "M1") (pin "1") (pinfunction "1_1") (pintype "input+no_connect"))
    )
    (net (code "45") (name "unconnected-(M2-Pad1)") (class "Default")
      (node (ref "M2") (pin "1") (pinfunction "1_1") (pintype "input+no_connect"))
    )
    (net (code "46") (name "unconnected-(M3-Pad1)") (class "Default")
      (node (ref "M3") (pin "1") (pinfunction "1_1") (pintype "input+no_connect"))
    )
    (net (code "47") (name "unconnected-(M4-Pad1)") (class "Default")
      (node (ref "M4") (pin "1") (pinfunction "1_1") (pintype "input+no_connect"))
    )
    (net (code "48") (name "unconnected-(P1-Pad3)") (class "Default")
      (node (ref "P1") (pin "3") (pinfunction "3_3") (pintype "input+no_connect"))
    )
    (net (code "49") (name "unconnected-(P1-Pad4)") (class "Default")
      (node (ref "P1") (pin "4") (pinfunction "4_4") (pintype "input+no_connect"))
    )
    (net (code "50") (name "unconnected-(U6-NC-Pad6)") (class "Default")
      (node (ref "U6") (pin "6") (pinfunction "NC_6") (pintype "input+no_connect"))
    )
  )
)
